# 8_can_transceiver.net
KiCad netlist of a schematic drawn in Altium Designer
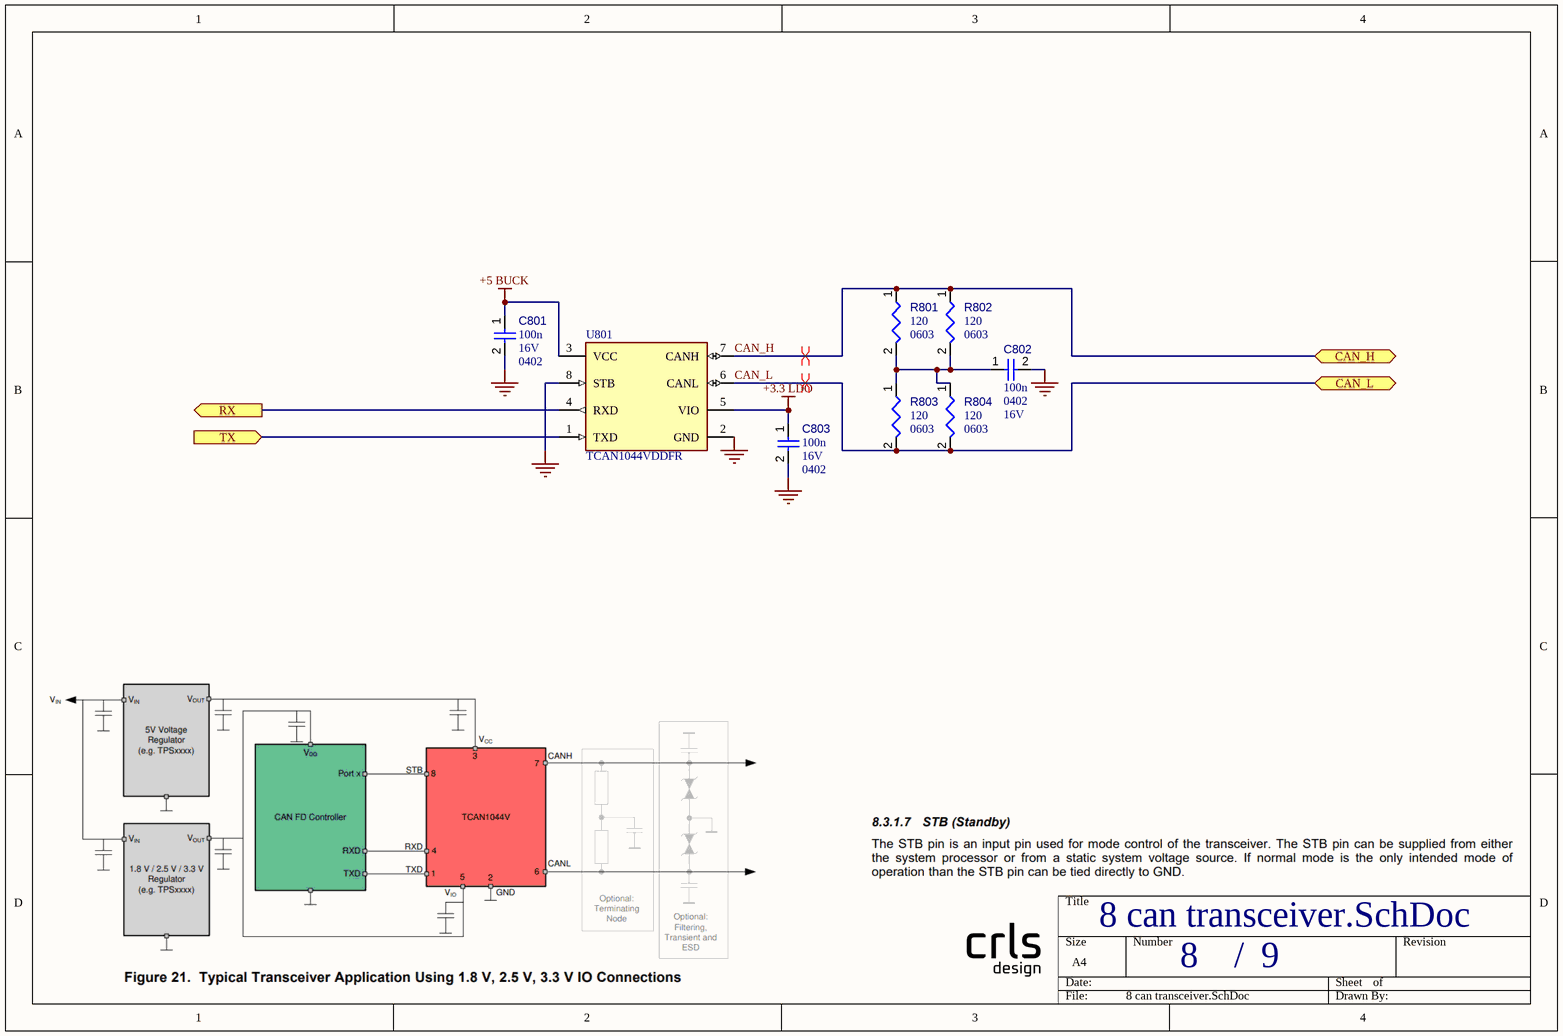
[diagram p0: 8 can transceiver.SchDoc]

(export (version "E")
  (design (tool "Eeschema 10.0.6"))
  (components
    (comp (ref "C801")
      (value "100n")
      (footprint "CAPC0402(1005)60_L")
      (description "Capacitor")
      (fields
        (field (name "CASE/PACKAGE") "0402")
        (field (name "VOLTAGE RATING") "16V")
        (field (name "Comment") "Capacitors,0402,100n,16V")
      )
      (libsource (lib "UBC Uncrewed Aircraft Systems") (part "CAP-NP-2"))
    )
    (comp (ref "C802")
      (value "100n")
      (footprint "CAPC0402(1005)60_L")
      (description "Capacitor")
      (fields
        (field (name "CASE/PACKAGE") "0402")
        (field (name "VOLTAGE RATING") "16V")
        (field (name "Comment") "Capacitors,0402,100n,16V")
      )
      (libsource (lib "UBC Uncrewed Aircraft Systems") (part "CAP-NP-2"))
    )
    (comp (ref "C803")
      (value "100n")
      (footprint "CAPC0402(1005)60_L")
      (description "Capacitor")
      (fields
        (field (name "CASE/PACKAGE") "0402")
        (field (name "VOLTAGE RATING") "16V")
        (field (name "Comment") "Capacitors,0402,100n,16V")
      )
      (libsource (lib "UBC Uncrewed Aircraft Systems") (part "CAP-NP-2"))
    )
    (comp (ref "R801")
      (value "120")
      (footprint "RESC0603(1608)_L")
      (description "Resistor")
      (fields
        (field (name "CASE/PACKAGE") "0603")
        (field (name "TOLERANCE") "1%")
        (field (name "Comment") "Resistors,0603,1%,120")
      )
      (libsource (lib "UBC Uncrewed Aircraft Systems") (part "RES-2"))
    )
    (comp (ref "R802")
      (value "120")
      (footprint "RESC0603(1608)_L")
      (description "Resistor")
      (fields
        (field (name "CASE/PACKAGE") "0603")
        (field (name "TOLERANCE") "1%")
        (field (name "Comment") "Resistors,0603,1%,120")
      )
      (libsource (lib "UBC Uncrewed Aircraft Systems") (part "RES-2"))
    )
    (comp (ref "R803")
      (value "120")
      (footprint "RESC0603(1608)_L")
      (description "Resistor")
      (fields
        (field (name "CASE/PACKAGE") "0603")
        (field (name "TOLERANCE") "1%")
        (field (name "Comment") "Resistors,0603,1%,120")
      )
      (libsource (lib "UBC Uncrewed Aircraft Systems") (part "RES-2"))
    )
    (comp (ref "R804")
      (value "120")
      (footprint "RESC0603(1608)_L")
      (description "Resistor")
      (fields
        (field (name "CASE/PACKAGE") "0603")
        (field (name "TOLERANCE") "1%")
        (field (name "Comment") "Resistors,0603,1%,120")
      )
      (libsource (lib "UBC Uncrewed Aircraft Systems") (part "RES-2"))
    )
    (comp (ref "U801")
      (value "TCAN1044VDDFR")
      (footprint "FP-DDF0008A-MFG")
      (description "IC TRANSCEIVER FULL 1/1 SOT23-8")
      (libsource (lib "Altium Content Vault") (part "07a38a3f496b147e1c88e0a0638d013"))
    )
  )
  (nets
    (net (code "1") (name "+3.3 LDO") (class "Default")
      (node (ref "C803") (pin "1") (pinfunction "1_1") (pintype "passive"))
      (node (ref "U801") (pin "5") (pinfunction "VIO_5") (pintype "power_in"))
    )
    (net (code "2") (name "+5 BUCK") (class "Default")
      (node (ref "C801") (pin "1") (pinfunction "1_1") (pintype "passive"))
      (node (ref "U801") (pin "3") (pinfunction "VCC_3") (pintype "power_in"))
    )
    (net (code "3") (name "/CAN_H") (class "Default")
      (node (ref "R801") (pin "1") (pinfunction "1_1") (pintype "passive"))
      (node (ref "R802") (pin "1") (pinfunction "1_1") (pintype "passive"))
      (node (ref "U801") (pin "7") (pinfunction "CANH_7") (pintype "bidirectional"))
    )
    (net (code "4") (name "/CAN_L") (class "Default")
      (node (ref "R803") (pin "2") (pinfunction "2_2") (pintype "passive"))
      (node (ref "R804") (pin "2") (pinfunction "2_2") (pintype "passive"))
      (node (ref "U801") (pin "6") (pinfunction "CANL_6") (pintype "bidirectional"))
    )
    (net (code "5") (name "/RX") (class "Default")
      (node (ref "U801") (pin "4") (pinfunction "RXD_4") (pintype "output"))
    )
    (net (code "6") (name "/TX") (class "Default")
      (node (ref "U801") (pin "1") (pinfunction "TXD_1") (pintype "input"))
    )
    (net (code "7") (name "GND") (class "Default")
      (node (ref "C801") (pin "2") (pinfunction "2_2") (pintype "passive"))
      (node (ref "C802") (pin "2") (pinfunction "2_2") (pintype "passive"))
      (node (ref "C803") (pin "2") (pinfunction "2_2") (pintype "passive"))
      (node (ref "U801") (pin "2") (pinfunction "GND_2") (pintype "power_in"))
      (node (ref "U801") (pin "8") (pinfunction "STB_8") (pintype "input"))
    )
    (net (code "8") (name "Net-(C802-Pad1)") (class "Default")
      (node (ref "C802") (pin "1") (pinfunction "1_1") (pintype "passive"))
      (node (ref "R801") (pin "2") (pinfunction "2_2") (pintype "passive"))
      (node (ref "R802") (pin "2") (pinfunction "2_2") (pintype "passive"))
      (node (ref "R803") (pin "1") (pinfunction "1_1") (pintype "passive"))
      (node (ref "R804") (pin "1") (pinfunction "1_1") (pintype "passive"))
    )
  )
)
